# Buck.net
KiCad netlist of a schematic drawn in Altium Designer
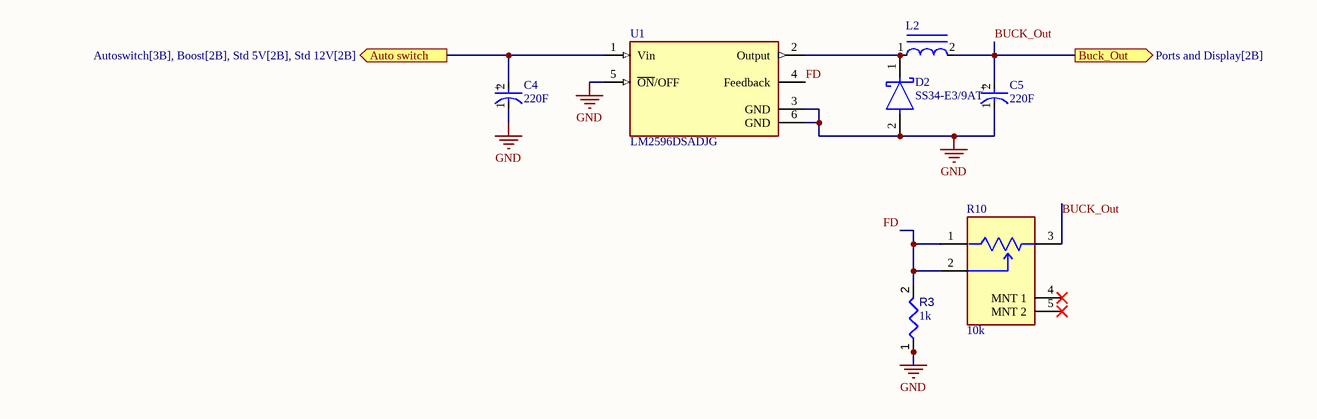
[diagram p0: Buck.SchDoc]

(export (version "E")
  (design (tool "Eeschema 10.0.6"))
  (components
    (comp (ref "C4")
      (value "220F")
      (footprint "FP-FTF-MFG")
      (fields (field (name "Comment") "Capacitors"))
      (libsource (lib "Vedant Ashtankar") (part "203bc49f2ac43e59fd269a8c329ed05"))
    )
    (comp (ref "C5")
      (value "220F")
      (footprint "FP-FTF-MFG")
      (fields (field (name "Comment") "Capacitors"))
      (libsource (lib "Vedant Ashtankar") (part "203bc49f2ac43e59fd269a8c329ed05"))
    )
    (comp (ref "D2")
      (value "SS34-E3/9AT")
      (footprint "FP-SMC-MFG")
      (description "Rectifier Diode, Schottky, 1 Phase, 1 Element, 3A, 40V V(RRM), Silicon, DO-214AB")
      (libsource (lib "Vedant Ashtankar") (part "c1678fac7984e62e0809fbf79c06691"))
    )
    (comp (ref "L2")
      (value "DR127-330-R")
      (footprint "FP-DR127-MFG")
      (description "General Purpose Inductor, 33uH, 20%, 1 Element, Ferrite-Core, SMD, 4949")
      (fields (field (name "TOLERANCE") "20%"))
      (libsource (lib "Vedant Ashtankar") (part "595efa879b4242f50b2b19a2702faec"))
    )
    (comp (ref "R3")
      (value "1k")
      (footprint "RESC0805(2012)_L")
      (description "1K 0.125W 5% 0805 (2012 Metric)  SMD")
      (fields (field (name "TOLERANCE") "5%") (field (name "POWER") "125mW"))
      (libsource (lib "Vedant Ashtankar") (part "1KR5J"))
    )
    (comp (ref "R10")
      (value "10k")
      (footprint "FP-PTV09A-4-MFG")
      (description "Potentiometer, Carbon, 0.05W, 10000ohm, 20V, 20% +/-Tol, 3943")
      (fields (field (name "TOLERANCE") "20%") (field (name "POWER") "50mW"))
      (libsource (lib "Vedant Ashtankar") (part "705d11b747745a787204d796a5f3d12"))
    )
    (comp (ref "U1")
      (value "LM2596DSADJG")
      (footprint "FP-936A-02-MFG")
      (description "Switching Regulator, Voltage-mode, 7.5A, 180kHz Switching Freq-Max, PSSO5")
      (libsource (lib "Vedant Ashtankar") (part "6e009c68f80b765d55aa2e30e527964"))
    )
  )
  (nets
    (net (code "1") (name "/Auto switch") (class "Default")
      (node (ref "C4") (pin "2") (pinfunction "A_2") (pintype "passive"))
      (node (ref "U1") (pin "1") (pinfunction "Vin_1") (pintype "input"))
    )
    (net (code "2") (name "/BUCK_Out") (class "Default")
      (node (ref "C5") (pin "2") (pinfunction "A_2") (pintype "passive"))
      (node (ref "L2") (pin "2") (pinfunction "2_2") (pintype "passive"))
      (node (ref "R10") (pin "3") (pinfunction "3_3") (pintype "passive"))
    )
    (net (code "3") (name "/FD") (class "Default")
      (node (ref "R10") (pin "1") (pinfunction "1_1") (pintype "passive"))
      (node (ref "R10") (pin "2") (pinfunction "2_2") (pintype "passive"))
      (node (ref "R3") (pin "2") (pinfunction "2_2") (pintype "passive"))
      (node (ref "U1") (pin "4") (pinfunction "Feedback_4") (pintype "passive"))
    )
    (net (code "4") (name "GND") (class "Default")
      (node (ref "C4") (pin "1") (pinfunction "C_1") (pintype "passive"))
      (node (ref "C5") (pin "1") (pinfunction "C_1") (pintype "passive"))
      (node (ref "D2") (pin "2") (pinfunction "A_2") (pintype "passive"))
      (node (ref "R3") (pin "1") (pinfunction "1_1") (pintype "passive"))
      (node (ref "U1") (pin "3") (pinfunction "GND_3") (pintype "power_in"))
      (node (ref "U1") (pin "5") (pinfunction "~{ON}/OFF_5") (pintype "input"))
      (node (ref "U1") (pin "6") (pinfunction "GND_6") (pintype "power_in"))
    )
    (net (code "5") (name "Net-(D2-C)") (class "Default")
      (node (ref "D2") (pin "1") (pinfunction "C_1") (pintype "passive"))
      (node (ref "L2") (pin "1") (pinfunction "1_1") (pintype "passive"))
      (node (ref "U1") (pin "2") (pinfunction "Output_2") (pintype "output"))
    )
    (net (code "6") (name "unconnected-(R10-MNT_1-Pad4)") (class "Default")
      (node (ref "R10") (pin "4") (pinfunction "MNT_1_4") (pintype "passive+no_connect"))
    )
    (net (code "7") (name "unconnected-(R10-MNT_2-Pad5)") (class "Default")
      (node (ref "R10") (pin "5") (pinfunction "MNT_2_5") (pintype "passive+no_connect"))
    )
  )
)
